# Current_Controller.net
KiCad netlist of a schematic drawn in Altium Designer
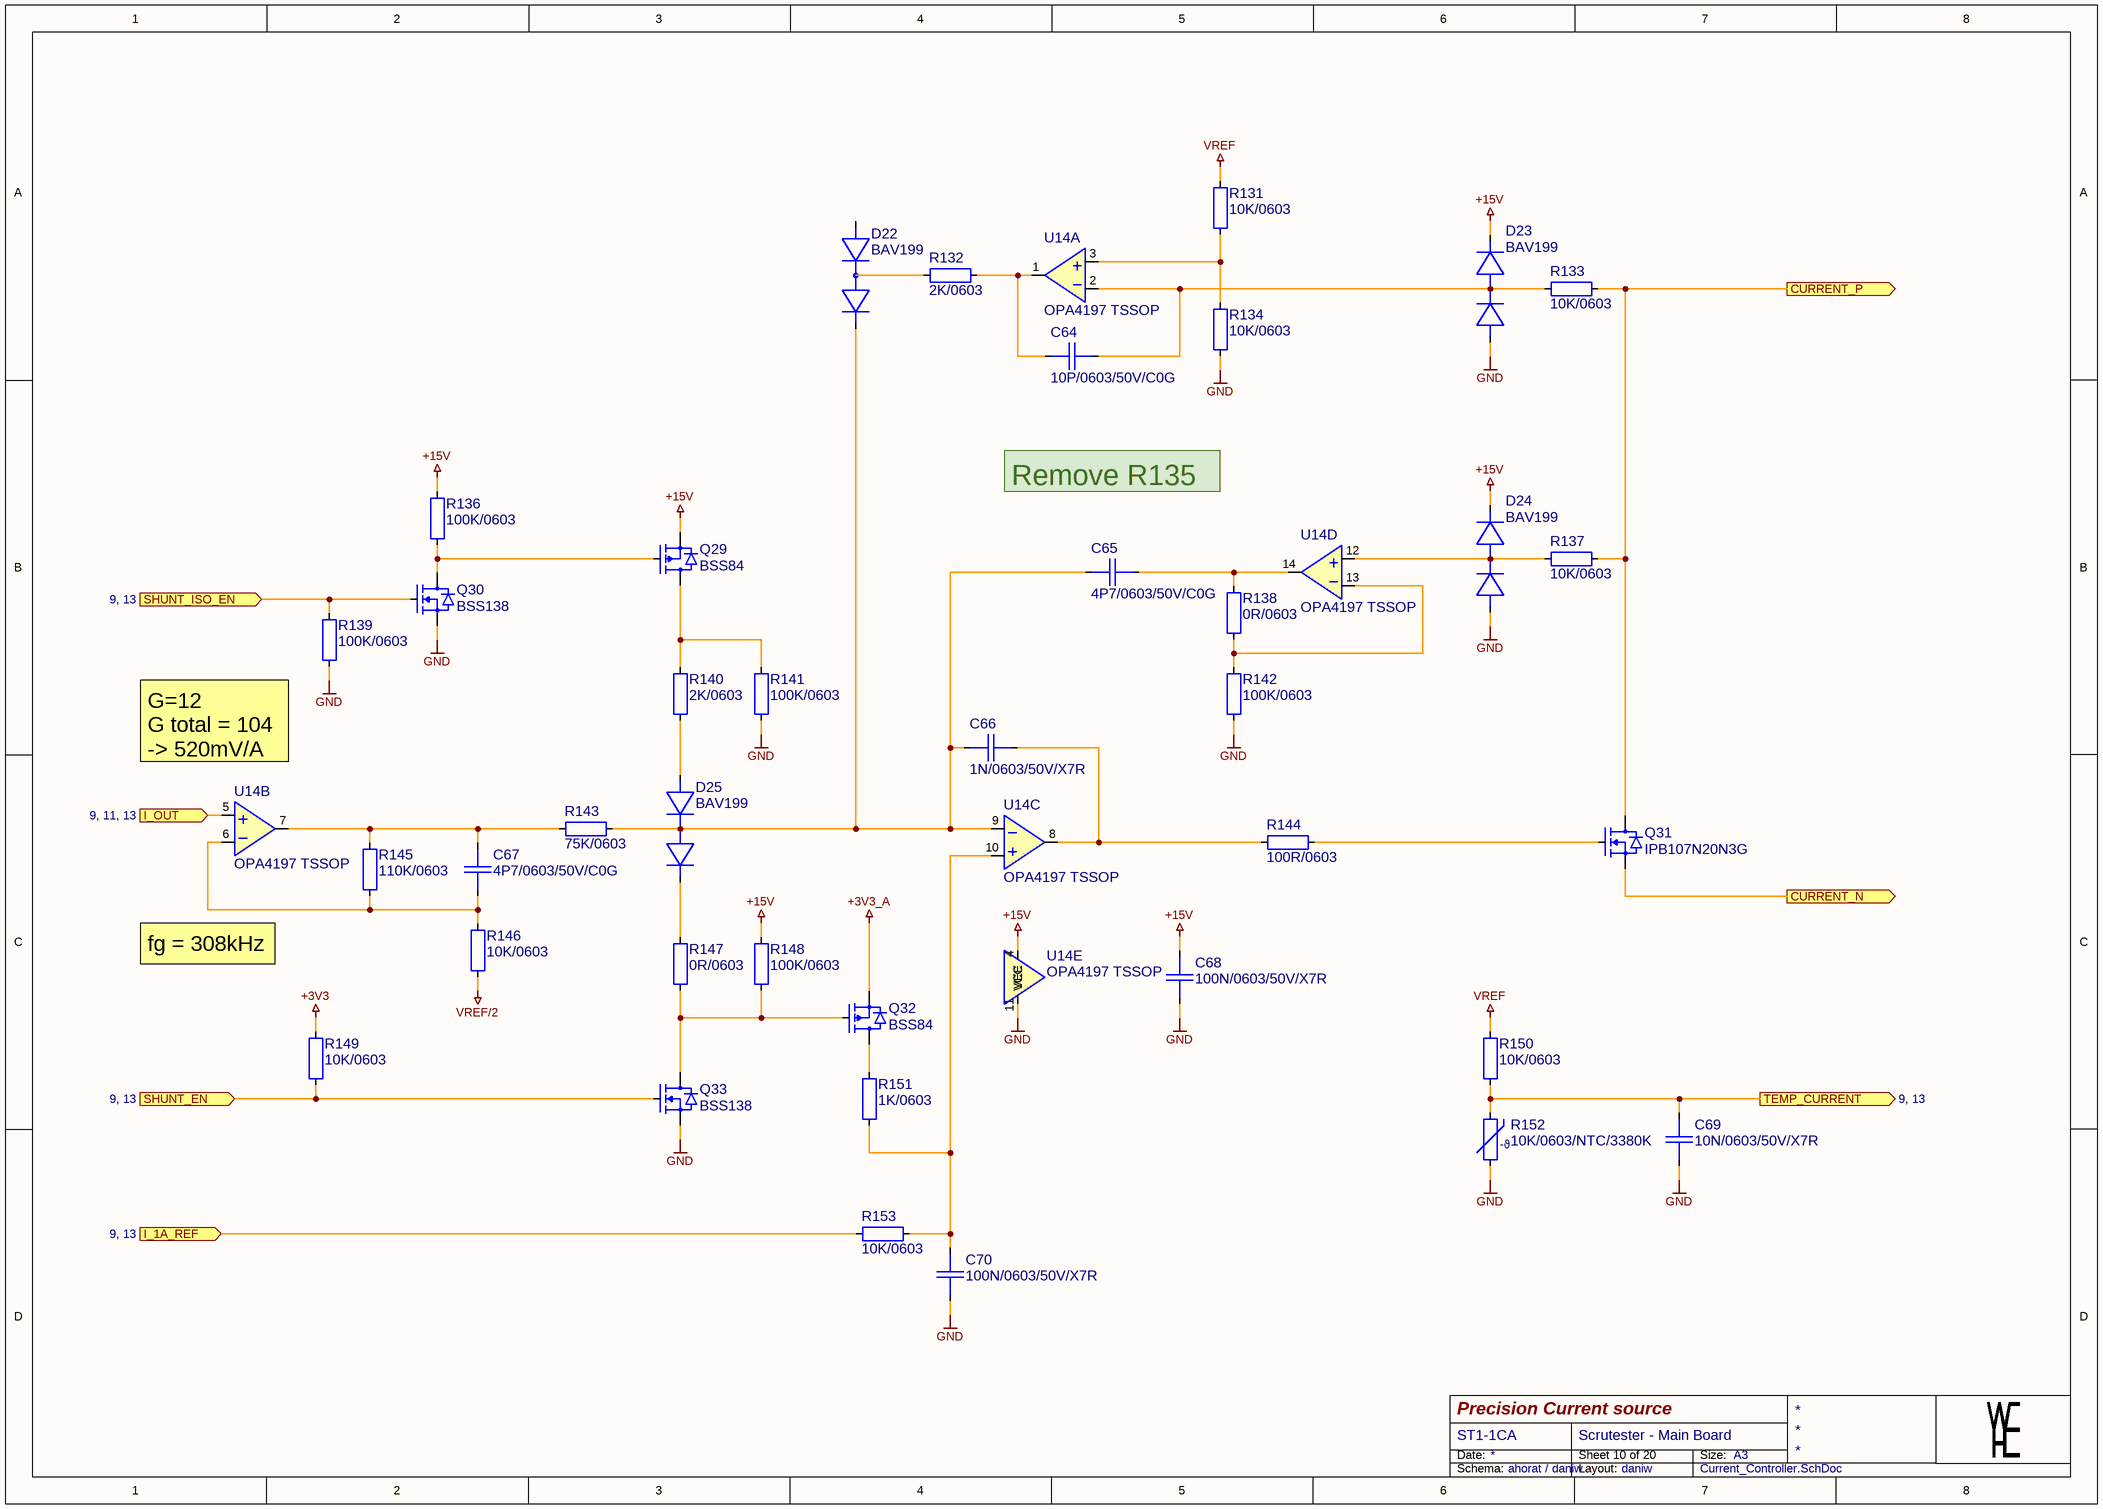
[diagram p0: Current_Controller.SchDoc]

(export (version "E")
  (design (tool "Eeschema 10.0.6"))
  (components
    (comp (ref "C64")
      (value "10P/0603/50V/C0G")
      (footprint "CAP0603_C0G")
      (description "CAP SM 0603 10pF 50V C0G")
      (fields (field (name "MANUFACTURER") "GENERIC"))
      (libsource (lib "daniw_altium_lib") (part "C"))
    )
    (comp (ref "C65")
      (value "4P7/0603/50V/C0G")
      (footprint "CAP0603_C0G")
      (description "CAP SM 0603 4.7pF 50V C0G")
      (fields (field (name "MANUFACTURER") "GENERIC"))
      (libsource (lib "daniw_altium_lib") (part "C"))
    )
    (comp (ref "C66")
      (value "1N/0603/50V/X7R")
      (footprint "CAP0603_X7R")
      (description "CAP SM 0603 1.0nF 50V X7R")
      (fields (field (name "MANUFACTURER") "GENERIC"))
      (libsource (lib "daniw_altium_lib") (part "C"))
    )
    (comp (ref "C67")
      (value "4P7/0603/50V/C0G")
      (footprint "CAP0603_C0G")
      (description "CAP SM 0603 4.7pF 50V C0G")
      (fields (field (name "MANUFACTURER") "GENERIC"))
      (libsource (lib "daniw_altium_lib") (part "C"))
    )
    (comp (ref "C68")
      (value "100N/0603/50V/X7R")
      (footprint "CAP0603_X7R")
      (description "CAP SM 0603 100nF 50V X7R")
      (fields (field (name "MANUFACTURER") "GENERIC"))
      (libsource (lib "daniw_altium_lib") (part "C"))
    )
    (comp (ref "C69")
      (value "10N/0603/50V/X7R")
      (footprint "CAP0603_X7R")
      (description "CAP SM 0603 10nF 50V X7R")
      (fields (field (name "MANUFACTURER") "GENERIC"))
      (libsource (lib "daniw_altium_lib") (part "C"))
    )
    (comp (ref "C70")
      (value "100N/0603/50V/X7R")
      (footprint "CAP0603_X7R")
      (description "CAP SM 0603 100nF 50V X7R")
      (fields (field (name "MANUFACTURER") "GENERIC"))
      (libsource (lib "daniw_altium_lib") (part "C"))
    )
    (comp (ref "D22")
      (value "BAV199")
      (footprint "SOT2395P280X125-3-SE")
      (description "Silicon Low Leakage Diode 85V")
      (fields (field (name "MANUFACTURER") "Infineon Technologies"))
      (libsource (lib "daniw_altium_lib") (part "D_Serie"))
    )
    (comp (ref "D23")
      (value "BAV199")
      (footprint "SOT2395P280X125-3-SE")
      (description "Silicon Low Leakage Diode 85V")
      (fields (field (name "MANUFACTURER") "Infineon Technologies"))
      (libsource (lib "daniw_altium_lib") (part "D_Serie"))
    )
    (comp (ref "D24")
      (value "BAV199")
      (footprint "SOT2395P280X125-3-SE")
      (description "Silicon Low Leakage Diode 85V")
      (fields (field (name "MANUFACTURER") "Infineon Technologies"))
      (libsource (lib "daniw_altium_lib") (part "D_Serie"))
    )
    (comp (ref "D25")
      (value "BAV199")
      (footprint "SOT2395P280X125-3-SE")
      (description "Silicon Low Leakage Diode 85V")
      (fields (field (name "MANUFACTURER") "Infineon Technologies"))
      (libsource (lib "daniw_altium_lib") (part "D_Serie"))
    )
    (comp (ref "Q29")
      (value "BSS84")
      (footprint "SOT2395P280X125-3-SE")
      (description "50V P-Channel MOSFET")
      (fields (field (name "MANUFACTURER") "GENERIC"))
      (libsource (lib "daniw_altium_lib") (part "MOSFET_P_G1_D3_S2"))
    )
    (comp (ref "Q30")
      (value "BSS138")
      (footprint "SOT2395P280X125-3-SE")
      (description "N-Kanal 50 V 220mA (Ta) 350mW (Ta) Oberflächenmontage SOT-23")
      (fields (field (name "MANUFACTURER") "GENERIC"))
      (libsource (lib "daniw_altium_lib") (part "MOSFET_N_G1_D3_S2"))
    )
    (comp (ref "Q31")
      (value "IPB107N20N3G")
      (footprint "TO254P1530X1035-3")
      (description "200V 88A 300W 10.7mΩ@10V,88A 4V 1 N-channel TO-263-3 MOSFETs ROHS")
      (fields (field (name "MANUFACTURER") "Infineon Technologies"))
      (libsource (lib "daniw_altium_lib") (part "MOSFET_N_G1_D3_S2"))
    )
    (comp (ref "Q32")
      (value "BSS84")
      (footprint "SOT2395P280X125-3-SE")
      (description "50V P-Channel MOSFET")
      (fields (field (name "MANUFACTURER") "GENERIC"))
      (libsource (lib "daniw_altium_lib") (part "MOSFET_P_G1_D3_S2"))
    )
    (comp (ref "Q33")
      (value "BSS138")
      (footprint "SOT2395P280X125-3-SE")
      (description "N-Kanal 50 V 220mA (Ta) 350mW (Ta) Oberflächenmontage SOT-23")
      (fields (field (name "MANUFACTURER") "GENERIC"))
      (libsource (lib "daniw_altium_lib") (part "MOSFET_N_G1_D3_S2"))
    )
    (comp (ref "R131")
      (value "10K/0603")
      (footprint "R0603-0.40-WW")
      (description "RES SM 0603 10K")
      (fields (field (name "MANUFACTURER") "GENERIC"))
      (libsource (lib "daniw_altium_lib") (part "R"))
    )
    (comp (ref "R132")
      (value "2K/0603")
      (footprint "R0603-0.40-WW")
      (description "RES SM 0603 2K")
      (fields (field (name "MANUFACTURER") "GENERIC"))
      (libsource (lib "daniw_altium_lib") (part "R"))
    )
    (comp (ref "R133")
      (value "10K/0603")
      (footprint "R0603-0.40-WW")
      (description "RES SM 0603 10K")
      (fields (field (name "MANUFACTURER") "GENERIC"))
      (libsource (lib "daniw_altium_lib") (part "R"))
    )
    (comp (ref "R134")
      (value "10K/0603")
      (footprint "R0603-0.40-WW")
      (description "RES SM 0603 10K")
      (fields (field (name "MANUFACTURER") "GENERIC"))
      (libsource (lib "daniw_altium_lib") (part "R"))
    )
    (comp (ref "R136")
      (value "100K/0603")
      (footprint "R0603-0.40-WW")
      (description "RES SM 0603 100K")
      (fields (field (name "MANUFACTURER") "GENERIC"))
      (libsource (lib "daniw_altium_lib") (part "R"))
    )
    (comp (ref "R137")
      (value "10K/0603")
      (footprint "R0603-0.40-WW")
      (description "RES SM 0603 10K")
      (fields (field (name "MANUFACTURER") "GENERIC"))
      (libsource (lib "daniw_altium_lib") (part "R"))
    )
    (comp (ref "R138")
      (value "0R/0603")
      (footprint "R0603-0.40-WW")
      (description "RES SM 0603 0R")
      (fields (field (name "MANUFACTURER") "GENERIC"))
      (libsource (lib "daniw_altium_lib") (part "R"))
    )
    (comp (ref "R139")
      (value "100K/0603")
      (footprint "R0603-0.40-WW")
      (description "RES SM 0603 100K")
      (fields (field (name "MANUFACTURER") "GENERIC"))
      (libsource (lib "daniw_altium_lib") (part "R"))
    )
    (comp (ref "R140")
      (value "2K/0603")
      (footprint "R0603-0.40-WW")
      (description "RES SM 0603 2K")
      (fields (field (name "MANUFACTURER") "GENERIC"))
      (libsource (lib "daniw_altium_lib") (part "R"))
    )
    (comp (ref "R141")
      (value "100K/0603")
      (footprint "R0603-0.40-WW")
      (description "RES SM 0603 100K")
      (fields (field (name "MANUFACTURER") "GENERIC"))
      (libsource (lib "daniw_altium_lib") (part "R"))
    )
    (comp (ref "R142")
      (value "100K/0603")
      (footprint "R0603-0.40-WW")
      (description "RES SM 0603 100K")
      (fields (field (name "MANUFACTURER") "GENERIC"))
      (libsource (lib "daniw_altium_lib") (part "R"))
    )
    (comp (ref "R143")
      (value "75K/0603")
      (footprint "R0603-0.40-WW")
      (description "RES SM 0603 75K")
      (fields (field (name "MANUFACTURER") "GENERIC"))
      (libsource (lib "daniw_altium_lib") (part "R"))
    )
    (comp (ref "R144")
      (value "100R/0603")
      (footprint "R0603-0.40-WW")
      (description "RES SM 0603 100R")
      (fields (field (name "MANUFACTURER") "GENERIC"))
      (libsource (lib "daniw_altium_lib") (part "R"))
    )
    (comp (ref "R145")
      (value "110K/0603")
      (footprint "R0603-0.40-WW")
      (description "RES SM 0603 110K")
      (fields (field (name "MANUFACTURER") "GENERIC"))
      (libsource (lib "daniw_altium_lib") (part "R"))
    )
    (comp (ref "R146")
      (value "10K/0603")
      (footprint "R0603-0.40-WW")
      (description "RES SM 0603 10K")
      (fields (field (name "MANUFACTURER") "GENERIC"))
      (libsource (lib "daniw_altium_lib") (part "R"))
    )
    (comp (ref "R147")
      (value "0R/0603")
      (footprint "R0603-0.40-WW")
      (description "RES SM 0603 0R")
      (fields (field (name "MANUFACTURER") "GENERIC"))
      (libsource (lib "daniw_altium_lib") (part "R"))
    )
    (comp (ref "R148")
      (value "100K/0603")
      (footprint "R0603-0.40-WW")
      (description "RES SM 0603 100K")
      (fields (field (name "MANUFACTURER") "GENERIC"))
      (libsource (lib "daniw_altium_lib") (part "R"))
    )
    (comp (ref "R149")
      (value "10K/0603")
      (footprint "R0603-0.40-WW")
      (description "RES SM 0603 10K")
      (fields (field (name "MANUFACTURER") "GENERIC"))
      (libsource (lib "daniw_altium_lib") (part "R"))
    )
    (comp (ref "R150")
      (value "10K/0603")
      (footprint "R0603-0.40-WW")
      (description "RES SM 0603 10K")
      (fields (field (name "MANUFACTURER") "GENERIC"))
      (libsource (lib "daniw_altium_lib") (part "R"))
    )
    (comp (ref "R151")
      (value "1K/0603")
      (footprint "R0603-0.40-WW")
      (description "RES SM 0603 1K")
      (fields (field (name "MANUFACTURER") "GENERIC"))
      (libsource (lib "daniw_altium_lib") (part "R"))
    )
    (comp (ref "R152")
      (value "10K/0603/NTC/3380K")
      (footprint "R0603-0.40-WW")
      (description "RES NTC SM 0603 10K")
      (fields (field (name "MANUFACTURER") "GENERIC"))
      (libsource (lib "daniw_altium_lib") (part "R_NTC"))
    )
    (comp (ref "R153")
      (value "10K/0603")
      (footprint "R0603-0.40-WW")
      (description "RES SM 0603 10K")
      (fields (field (name "MANUFACTURER") "GENERIC"))
      (libsource (lib "daniw_altium_lib") (part "R"))
    )
    (comp (ref "U14")
      (value "OPA4197 TSSOP")
      (footprint "SOP065P640X120-14NW")
      (description "OPA4197 36-V, Precision, Rail-to-Rail Input/Output, Low Offset Voltage, Operational Amplifiers")
      (fields (field (name "MANUFACTURER") "Texas Instruments"))
      (libsource (lib "daniw_altium_lib") (part "OPA4_O1-7-8-14_P3-5-10-12_N2-6-9-13_VCC4_VEE11"))
    )
  )
  (nets
    (net (code "1") (name "+3V3") (class "Default")
      (node (ref "R149") (pin "1") (pinfunction "1_1") (pintype "passive"))
    )
    (net (code "2") (name "+3V3_A") (class "Default")
      (node (ref "Q32") (pin "2") (pinfunction "SOURCE_2") (pintype "passive"))
    )
    (net (code "3") (name "+15V") (class "Default")
      (node (ref "C68") (pin "1") (pinfunction "1_1") (pintype "passive"))
      (node (ref "D23") (pin "2") (pinfunction "K2_2") (pintype "passive"))
      (node (ref "D24") (pin "2") (pinfunction "K2_2") (pintype "passive"))
      (node (ref "Q29") (pin "2") (pinfunction "SOURCE_2") (pintype "passive"))
      (node (ref "R136") (pin "1") (pinfunction "1_1") (pintype "passive"))
      (node (ref "R148") (pin "1") (pinfunction "1_1") (pintype "passive"))
      (node (ref "U14") (pin "4") (pinfunction "VCC_4") (pintype "passive"))
    )
    (net (code "4") (name "/CURRENT_N") (class "Default")
      (node (ref "Q31") (pin "2") (pinfunction "SOURCE_2") (pintype "passive"))
    )
    (net (code "5") (name "/CURRENT_P") (class "Default")
      (node (ref "Q31") (pin "3") (pinfunction "DRAIN_3") (pintype "passive"))
      (node (ref "R133") (pin "2") (pinfunction "2_2") (pintype "passive"))
      (node (ref "R137") (pin "2") (pinfunction "2_2") (pintype "passive"))
    )
    (net (code "6") (name "/I_1A_REF") (class "Default")
      (node (ref "R153") (pin "1") (pinfunction "1_1") (pintype "passive"))
    )
    (net (code "7") (name "/I_OUT") (class "Default")
      (node (ref "U14") (pin "5") (pinfunction "IN+_5") (pintype "passive"))
    )
    (net (code "8") (name "/SHUNT_EN") (class "Default")
      (node (ref "Q33") (pin "1") (pinfunction "GATE_1") (pintype "passive"))
      (node (ref "R149") (pin "2") (pinfunction "2_2") (pintype "passive"))
    )
    (net (code "9") (name "/SHUNT_ISO_EN") (class "Default")
      (node (ref "Q30") (pin "1") (pinfunction "GATE_1") (pintype "passive"))
      (node (ref "R139") (pin "1") (pinfunction "1_1") (pintype "passive"))
    )
    (net (code "10") (name "/TEMP_CURRENT") (class "Default")
      (node (ref "C69") (pin "1") (pinfunction "1_1") (pintype "passive"))
      (node (ref "R150") (pin "2") (pinfunction "2_2") (pintype "passive"))
      (node (ref "R152") (pin "1") (pinfunction "1_1") (pintype "passive"))
    )
    (net (code "11") (name "GND") (class "Default")
      (node (ref "C68") (pin "2") (pinfunction "2_2") (pintype "passive"))
      (node (ref "C69") (pin "2") (pinfunction "2_2") (pintype "passive"))
      (node (ref "C70") (pin "2") (pinfunction "2_2") (pintype "passive"))
      (node (ref "D23") (pin "1") (pinfunction "A1_1") (pintype "passive"))
      (node (ref "D24") (pin "1") (pinfunction "A1_1") (pintype "passive"))
      (node (ref "Q30") (pin "2") (pinfunction "SOURCE_2") (pintype "passive"))
      (node (ref "Q33") (pin "2") (pinfunction "SOURCE_2") (pintype "passive"))
      (node (ref "R134") (pin "2") (pinfunction "2_2") (pintype "passive"))
      (node (ref "R139") (pin "2") (pinfunction "2_2") (pintype "passive"))
      (node (ref "R141") (pin "2") (pinfunction "2_2") (pintype "passive"))
      (node (ref "R142") (pin "2") (pinfunction "2_2") (pintype "passive"))
      (node (ref "R152") (pin "2") (pinfunction "2_2") (pintype "passive"))
      (node (ref "U14") (pin "11") (pinfunction "VEE_11") (pintype "passive"))
    )
    (net (code "12") (name "Net-(D22-K1{slash}A2)") (class "Default")
      (node (ref "D22") (pin "3") (pinfunction "K1/A2_3") (pintype "passive"))
      (node (ref "R132") (pin "2") (pinfunction "2_2") (pintype "passive"))
    )
    (net (code "13") (name "Net-(D22-K2)") (class "Default")
      (node (ref "C65") (pin "1") (pinfunction "1_1") (pintype "passive"))
      (node (ref "C66") (pin "1") (pinfunction "1_1") (pintype "passive"))
      (node (ref "D22") (pin "2") (pinfunction "K2_2") (pintype "passive"))
      (node (ref "D25") (pin "3") (pinfunction "K1/A2_3") (pintype "passive"))
      (node (ref "R143") (pin "2") (pinfunction "2_2") (pintype "passive"))
      (node (ref "U14") (pin "9") (pinfunction "IN-_9") (pintype "passive"))
    )
    (net (code "14") (name "Net-(D23-K1{slash}A2)") (class "Default")
      (node (ref "C64") (pin "2") (pinfunction "2_2") (pintype "passive"))
      (node (ref "D23") (pin "3") (pinfunction "K1/A2_3") (pintype "passive"))
      (node (ref "R133") (pin "1") (pinfunction "1_1") (pintype "passive"))
      (node (ref "U14") (pin "2") (pinfunction "IN-_2") (pintype "passive"))
    )
    (net (code "15") (name "Net-(D24-K1{slash}A2)") (class "Default")
      (node (ref "D24") (pin "3") (pinfunction "K1/A2_3") (pintype "passive"))
      (node (ref "R137") (pin "1") (pinfunction "1_1") (pintype "passive"))
      (node (ref "U14") (pin "12") (pinfunction "IN+_12") (pintype "passive"))
    )
    (net (code "16") (name "Net-(D25-A1)") (class "Default")
      (node (ref "D25") (pin "1") (pinfunction "A1_1") (pintype "passive"))
      (node (ref "R140") (pin "2") (pinfunction "2_2") (pintype "passive"))
    )
    (net (code "17") (name "Net-(D25-K2)") (class "Default")
      (node (ref "D25") (pin "2") (pinfunction "K2_2") (pintype "passive"))
      (node (ref "R147") (pin "1") (pinfunction "1_1") (pintype "passive"))
    )
    (net (code "18") (name "Net-(Q29-DRAIN)") (class "Default")
      (node (ref "Q29") (pin "3") (pinfunction "DRAIN_3") (pintype "passive"))
      (node (ref "R140") (pin "1") (pinfunction "1_1") (pintype "passive"))
      (node (ref "R141") (pin "1") (pinfunction "1_1") (pintype "passive"))
    )
    (net (code "19") (name "Net-(Q29-GATE)") (class "Default")
      (node (ref "Q29") (pin "1") (pinfunction "GATE_1") (pintype "passive"))
      (node (ref "Q30") (pin "3") (pinfunction "DRAIN_3") (pintype "passive"))
      (node (ref "R136") (pin "2") (pinfunction "2_2") (pintype "passive"))
    )
    (net (code "20") (name "Net-(Q31-GATE)") (class "Default")
      (node (ref "Q31") (pin "1") (pinfunction "GATE_1") (pintype "passive"))
      (node (ref "R144") (pin "2") (pinfunction "2_2") (pintype "passive"))
    )
    (net (code "21") (name "Net-(Q32-DRAIN)") (class "Default")
      (node (ref "Q32") (pin "3") (pinfunction "DRAIN_3") (pintype "passive"))
      (node (ref "R151") (pin "1") (pinfunction "1_1") (pintype "passive"))
    )
    (net (code "22") (name "Net-(Q32-GATE)") (class "Default")
      (node (ref "Q32") (pin "1") (pinfunction "GATE_1") (pintype "passive"))
      (node (ref "Q33") (pin "3") (pinfunction "DRAIN_3") (pintype "passive"))
      (node (ref "R147") (pin "2") (pinfunction "2_2") (pintype "passive"))
      (node (ref "R148") (pin "2") (pinfunction "2_2") (pintype "passive"))
    )
    (net (code "23") (name "Net-(U14A-IN+)") (class "Default")
      (node (ref "R131") (pin "2") (pinfunction "2_2") (pintype "passive"))
      (node (ref "R134") (pin "1") (pinfunction "1_1") (pintype "passive"))
      (node (ref "U14") (pin "3") (pinfunction "IN+_3") (pintype "passive"))
    )
    (net (code "24") (name "Net-(U14A-OUT)") (class "Default")
      (node (ref "C64") (pin "1") (pinfunction "1_1") (pintype "passive"))
      (node (ref "R132") (pin "1") (pinfunction "1_1") (pintype "passive"))
      (node (ref "U14") (pin "1") (pinfunction "OUT_1") (pintype "passive"))
    )
    (net (code "25") (name "Net-(U14B-IN-)") (class "Default")
      (node (ref "C67") (pin "2") (pinfunction "2_2") (pintype "passive"))
      (node (ref "R145") (pin "2") (pinfunction "2_2") (pintype "passive"))
      (node (ref "R146") (pin "1") (pinfunction "1_1") (pintype "passive"))
      (node (ref "U14") (pin "6") (pinfunction "IN-_6") (pintype "passive"))
    )
    (net (code "26") (name "Net-(U14B-OUT)") (class "Default")
      (node (ref "C67") (pin "1") (pinfunction "1_1") (pintype "passive"))
      (node (ref "R143") (pin "1") (pinfunction "1_1") (pintype "passive"))
      (node (ref "R145") (pin "1") (pinfunction "1_1") (pintype "passive"))
      (node (ref "U14") (pin "7") (pinfunction "OUT_7") (pintype "passive"))
    )
    (net (code "27") (name "Net-(U14C-IN+)") (class "Default")
      (node (ref "C70") (pin "1") (pinfunction "1_1") (pintype "passive"))
      (node (ref "R151") (pin "2") (pinfunction "2_2") (pintype "passive"))
      (node (ref "R153") (pin "2") (pinfunction "2_2") (pintype "passive"))
      (node (ref "U14") (pin "10") (pinfunction "IN+_10") (pintype "passive"))
    )
    (net (code "28") (name "Net-(U14C-OUT)") (class "Default")
      (node (ref "C66") (pin "2") (pinfunction "2_2") (pintype "passive"))
      (node (ref "R144") (pin "1") (pinfunction "1_1") (pintype "passive"))
      (node (ref "U14") (pin "8") (pinfunction "OUT_8") (pintype "passive"))
    )
    (net (code "29") (name "Net-(U14D-IN-)") (class "Default")
      (node (ref "R138") (pin "2") (pinfunction "2_2") (pintype "passive"))
      (node (ref "R142") (pin "1") (pinfunction "1_1") (pintype "passive"))
      (node (ref "U14") (pin "13") (pinfunction "IN-_13") (pintype "passive"))
    )
    (net (code "30") (name "Net-(U14D-OUT)") (class "Default")
      (node (ref "C65") (pin "2") (pinfunction "2_2") (pintype "passive"))
      (node (ref "R138") (pin "1") (pinfunction "1_1") (pintype "passive"))
      (node (ref "U14") (pin "14") (pinfunction "OUT_14") (pintype "passive"))
    )
    (net (code "31") (name "VREF") (class "Default")
      (node (ref "R131") (pin "1") (pinfunction "1_1") (pintype "passive"))
      (node (ref "R150") (pin "1") (pinfunction "1_1") (pintype "passive"))
    )
    (net (code "32") (name "VREF{slash}2") (class "Default")
      (node (ref "R146") (pin "2") (pinfunction "2_2") (pintype "passive"))
    )
    (net (code "33") (name "unconnected-(D22-A1-Pad1)") (class "Default")
      (node (ref "D22") (pin "1") (pinfunction "A1_1") (pintype "passive"))
    )
  )
)
